# SD_Card.net
KiCad netlist of a schematic drawn in Altium Designer
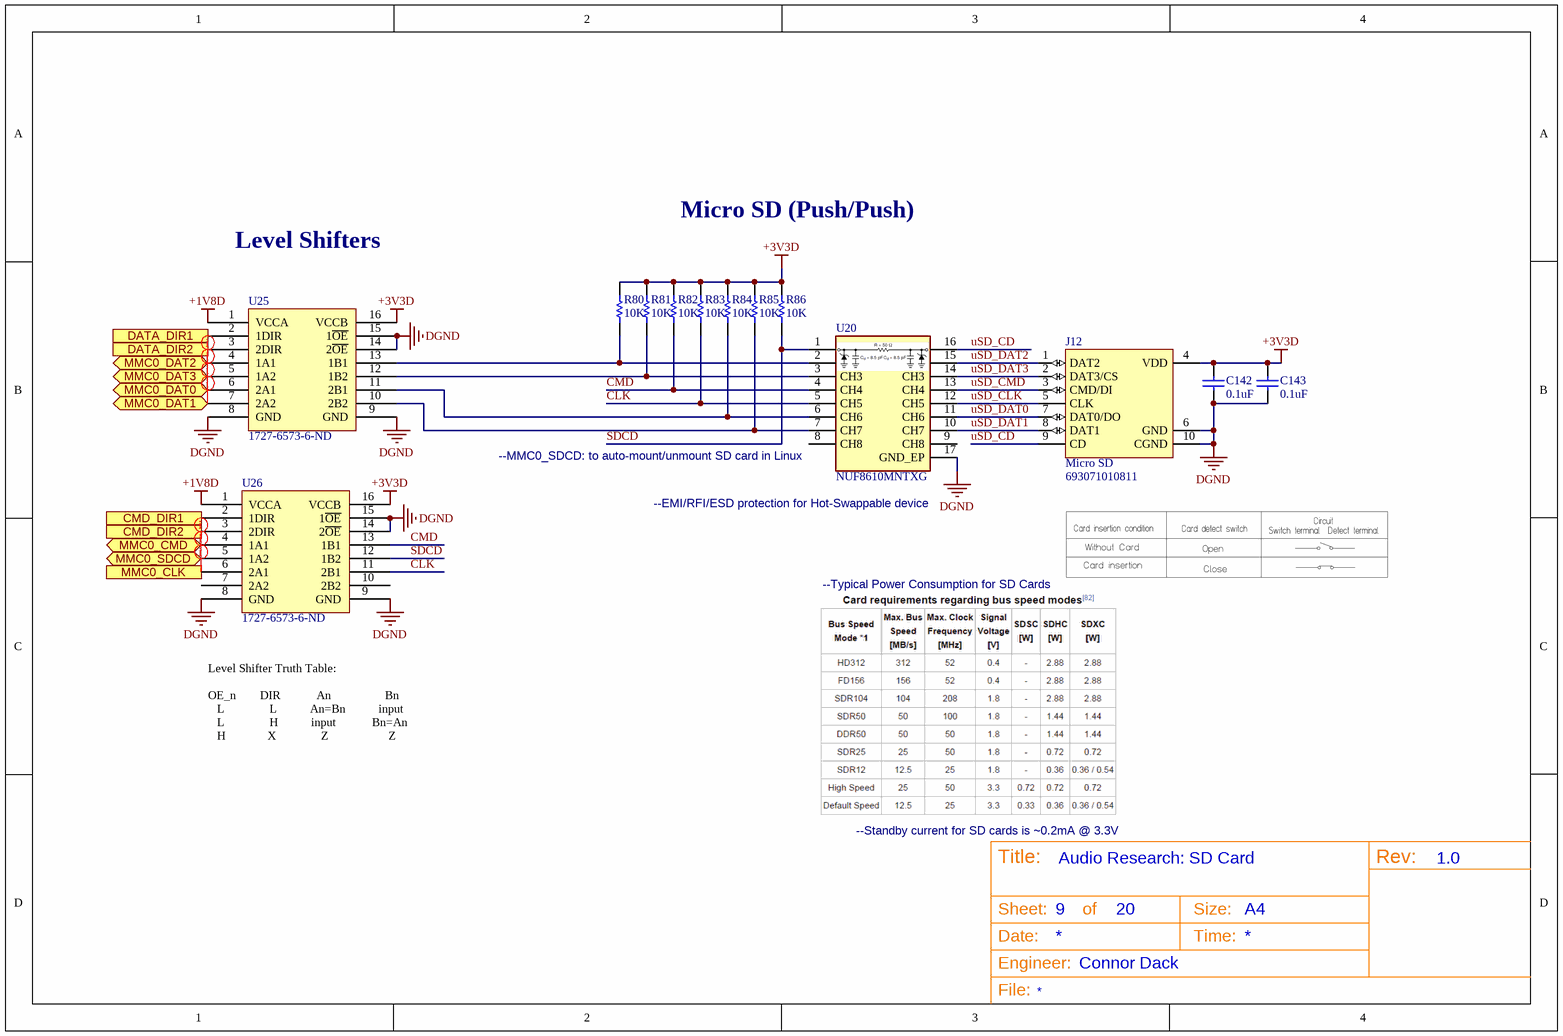
[diagram p0: SD_Card.SchDoc]

(export (version "E")
  (design (tool "Eeschema 10.0.6"))
  (components
    (comp (ref "C142")
      (value "CL10F104ZO8NNNC")
      (footprint "3-0603_L")
      (description "CAP CER 0.1UF 16V Y5V 0603")
      (fields
        (field (name "MANUFACTURER") "Samsung")
        (field (name "TOLERANCE") "80%")
        (field (name "CAPACITANCE") "0.1uF")
      )
      (libsource (lib "Schematic_Components_CD") (part "CL10F104ZO8NNNC"))
    )
    (comp (ref "C143")
      (value "CL10F104ZO8NNNC")
      (footprint "3-0603_L")
      (description "CAP CER 0.1UF 16V Y5V 0603")
      (fields
        (field (name "MANUFACTURER") "Samsung")
        (field (name "TOLERANCE") "80%")
        (field (name "CAPACITANCE") "0.1uF")
      )
      (libsource (lib "Schematic_Components_CD") (part "CL10F104ZO8NNNC"))
    )
    (comp (ref "J12")
      (value "Micro SD")
      (footprint "693071010811")
      (description "CONN MICRO SD 8 POS SMD")
      (fields
        (field (name "MANUFACTURER") "Wurth Electronics Inc")
        (field (name "MANUFACTURER PART NUMBER") "693071010811")
      )
      (libsource (lib "Schematic_Components") (part "693071010811_mmc"))
    )
    (comp (ref "R80")
      (value "ERJ-2GEJ103X")
      (footprint "2-0402_R_L")
      (description "RES 10K OHM 1/10W 5% 0402 SMD")
      (fields
        (field (name "MANUFACTURER") "Panasonic - ECG")
        (field (name "TOLERANCE") "±5%")
        (field (name "RESISTANCE (OHMS)") "10K")
      )
      (libsource (lib "Schematic_Components") (part "ERJ-2GEJ103X"))
    )
    (comp (ref "R81")
      (value "ERJ-2GEJ103X")
      (footprint "2-0402_R_L")
      (description "RES 10K OHM 1/10W 5% 0402 SMD")
      (fields
        (field (name "MANUFACTURER") "Panasonic - ECG")
        (field (name "TOLERANCE") "±5%")
        (field (name "RESISTANCE (OHMS)") "10K")
      )
      (libsource (lib "Schematic_Components") (part "ERJ-2GEJ103X"))
    )
    (comp (ref "R82")
      (value "ERJ-2GEJ103X")
      (footprint "2-0402_R_L")
      (description "RES 10K OHM 1/10W 5% 0402 SMD")
      (fields
        (field (name "MANUFACTURER") "Panasonic - ECG")
        (field (name "TOLERANCE") "±5%")
        (field (name "RESISTANCE (OHMS)") "10K")
      )
      (libsource (lib "Schematic_Components") (part "ERJ-2GEJ103X"))
    )
    (comp (ref "R83")
      (value "ERJ-2GEJ103X")
      (footprint "2-0402_R_L")
      (description "RES 10K OHM 1/10W 5% 0402 SMD")
      (fields
        (field (name "MANUFACTURER") "Panasonic - ECG")
        (field (name "TOLERANCE") "±5%")
        (field (name "RESISTANCE (OHMS)") "10K")
      )
      (libsource (lib "Schematic_Components") (part "ERJ-2GEJ103X"))
    )
    (comp (ref "R84")
      (value "ERJ-2GEJ103X")
      (footprint "2-0402_R_L")
      (description "RES 10K OHM 1/10W 5% 0402 SMD")
      (fields
        (field (name "MANUFACTURER") "Panasonic - ECG")
        (field (name "TOLERANCE") "±5%")
        (field (name "RESISTANCE (OHMS)") "10K")
      )
      (libsource (lib "Schematic_Components") (part "ERJ-2GEJ103X"))
    )
    (comp (ref "R85")
      (value "ERJ-2GEJ103X")
      (footprint "2-0402_R_L")
      (description "RES 10K OHM 1/10W 5% 0402 SMD")
      (fields
        (field (name "MANUFACTURER") "Panasonic - ECG")
        (field (name "TOLERANCE") "±5%")
        (field (name "RESISTANCE (OHMS)") "10K")
      )
      (libsource (lib "Schematic_Components") (part "ERJ-2GEJ103X"))
    )
    (comp (ref "R86")
      (value "ERJ-2GEJ103X")
      (footprint "2-0402_R_L")
      (description "RES 10K OHM 1/10W 5% 0402 SMD")
      (fields
        (field (name "MANUFACTURER") "Panasonic - ECG")
        (field (name "TOLERANCE") "±5%")
        (field (name "RESISTANCE (OHMS)") "10K")
      )
      (libsource (lib "Schematic_Components") (part "ERJ-2GEJ103X"))
    )
    (comp (ref "U20")
      (value "NUF8610MNTXG")
      (footprint "ONSC-DFN-16-506AC_V")
      (description "IC EMI FILTER 8CH 16-DFN")
      (fields
        (field (name "MANUFACTURER") "ON Semiconductor")
        (field (name "MANUFACTURER PART NUMBER") "NUF8610MNTXG")
      )
      (libsource (lib "Schematic_Components") (part "NUF8610MNTXG"))
    )
    (comp (ref "U25")
      (value "IC TXRX 4BIT DUAL 3ST 16TSSOP")
      (footprint "TSOP65P640X120-16N")
      (description "Voltage Level Translator Bidirectional 2 Circuit 2 Channel 380Mbps 16-TSSOP")
      (fields
        (field (name "MANUFACTURER") "NXP Semiconductors")
        (field (name "SUPPLIER PART NUMBER 1") "1727-6573-6-ND")
        (field (name "MANUFACTURER PART NUMBER") "74AVC4T245PW,118")
      )
      (libsource (lib "Schematic_Components_CD") (part "74AVC4T245PW,118"))
    )
    (comp (ref "U26")
      (value "IC TXRX 4BIT DUAL 3ST 16TSSOP")
      (footprint "TSOP65P640X120-16N")
      (description "Voltage Level Translator Bidirectional 2 Circuit 2 Channel 380Mbps 16-TSSOP")
      (fields
        (field (name "MANUFACTURER") "NXP Semiconductors")
        (field (name "SUPPLIER PART NUMBER 1") "1727-6573-6-ND")
        (field (name "MANUFACTURER PART NUMBER") "74AVC4T245PW,118")
      )
      (libsource (lib "Schematic_Components_CD") (part "74AVC4T245PW,118"))
    )
  )
  (nets
    (net (code "1") (name "+1V8D") (class "Default")
      (node (ref "U25") (pin "1") (pinfunction "VCCA_1") (pintype "passive"))
      (node (ref "U26") (pin "1") (pinfunction "VCCA_1") (pintype "passive"))
    )
    (net (code "2") (name "+3V3D") (class "Default")
      (node (ref "C142") (pin "1") (pinfunction "1_1") (pintype "passive"))
      (node (ref "C143") (pin "1") (pinfunction "1_1") (pintype "passive"))
      (node (ref "J12") (pin "4") (pinfunction "VDD_4") (pintype "power_in"))
      (node (ref "R80") (pin "2") (pinfunction "2_2") (pintype "passive"))
      (node (ref "R81") (pin "2") (pinfunction "2_2") (pintype "passive"))
      (node (ref "R82") (pin "2") (pinfunction "2_2") (pintype "passive"))
      (node (ref "R83") (pin "2") (pinfunction "2_2") (pintype "passive"))
      (node (ref "R84") (pin "2") (pinfunction "2_2") (pintype "passive"))
      (node (ref "R85") (pin "2") (pinfunction "2_2") (pintype "passive"))
      (node (ref "R86") (pin "2") (pinfunction "2_2") (pintype "passive"))
      (node (ref "U25") (pin "16") (pinfunction "VCCB_16") (pintype "passive"))
      (node (ref "U26") (pin "16") (pinfunction "VCCB_16") (pintype "passive"))
    )
    (net (code "3") (name "/CLK") (class "Default")
      (node (ref "R83") (pin "1") (pinfunction "1_1") (pintype "passive"))
      (node (ref "U20") (pin "5") (pinfunction "CH5_5") (pintype "passive"))
      (node (ref "U26") (pin "11") (pinfunction "2B1_11") (pintype "passive"))
    )
    (net (code "4") (name "/CMD") (class "Default")
      (node (ref "R82") (pin "1") (pinfunction "1_1") (pintype "passive"))
      (node (ref "U20") (pin "4") (pinfunction "CH4_4") (pintype "passive"))
      (node (ref "U26") (pin "13") (pinfunction "1B1_13") (pintype "passive"))
    )
    (net (code "5") (name "/CMD_DIR1") (class "Default")
      (node (ref "U26") (pin "2") (pinfunction "1DIR_2") (pintype "passive"))
    )
    (net (code "6") (name "/CMD_DIR2") (class "Default")
      (node (ref "U26") (pin "3") (pinfunction "2DIR_3") (pintype "passive"))
    )
    (net (code "7") (name "/DATA_DIR1") (class "Default")
      (node (ref "U25") (pin "2") (pinfunction "1DIR_2") (pintype "passive"))
    )
    (net (code "8") (name "/DATA_DIR2") (class "Default")
      (node (ref "U25") (pin "3") (pinfunction "2DIR_3") (pintype "passive"))
    )
    (net (code "9") (name "/MMC0_CLK") (class "Default")
      (node (ref "U26") (pin "6") (pinfunction "2A1_6") (pintype "passive"))
    )
    (net (code "10") (name "/MMC0_CMD") (class "Default")
      (node (ref "U26") (pin "4") (pinfunction "1A1_4") (pintype "passive"))
    )
    (net (code "11") (name "/MMC0_DAT0") (class "Default")
      (node (ref "U25") (pin "6") (pinfunction "2A1_6") (pintype "passive"))
    )
    (net (code "12") (name "/MMC0_DAT1") (class "Default")
      (node (ref "U25") (pin "7") (pinfunction "2A2_7") (pintype "passive"))
    )
    (net (code "13") (name "/MMC0_DAT2") (class "Default")
      (node (ref "U25") (pin "4") (pinfunction "1A1_4") (pintype "passive"))
    )
    (net (code "14") (name "/MMC0_DAT3") (class "Default")
      (node (ref "U25") (pin "5") (pinfunction "1A2_5") (pintype "passive"))
    )
    (net (code "15") (name "/MMC0_SDCD") (class "Default")
      (node (ref "U26") (pin "5") (pinfunction "1A2_5") (pintype "passive"))
    )
    (net (code "16") (name "/SDCD") (class "Default")
      (node (ref "R86") (pin "1") (pinfunction "1_1") (pintype "passive"))
      (node (ref "U20") (pin "1") (pinfunction "CH1_1") (pintype "passive"))
      (node (ref "U26") (pin "12") (pinfunction "1B2_12") (pintype "passive"))
    )
    (net (code "17") (name "/uSD_CD") (class "Default")
      (node (ref "J12") (pin "9") (pinfunction "CD_9") (pintype "passive"))
      (node (ref "U20") (pin "16") (pinfunction "CH1_16") (pintype "passive"))
    )
    (net (code "18") (name "/uSD_CLK") (class "Default")
      (node (ref "J12") (pin "5") (pinfunction "CLK_5") (pintype "passive"))
      (node (ref "U20") (pin "12") (pinfunction "CH5_12") (pintype "passive"))
    )
    (net (code "19") (name "/uSD_CMD") (class "Default")
      (node (ref "J12") (pin "3") (pinfunction "CMD/DI_3") (pintype "bidirectional"))
      (node (ref "U20") (pin "13") (pinfunction "CH4_13") (pintype "passive"))
    )
    (net (code "20") (name "/uSD_DAT0") (class "Default")
      (node (ref "J12") (pin "7") (pinfunction "DAT0/DO_7") (pintype "bidirectional"))
      (node (ref "U20") (pin "11") (pinfunction "CH6_11") (pintype "passive"))
    )
    (net (code "21") (name "/uSD_DAT1") (class "Default")
      (node (ref "J12") (pin "8") (pinfunction "DAT1_8") (pintype "bidirectional"))
      (node (ref "U20") (pin "10") (pinfunction "CH7_10") (pintype "passive"))
    )
    (net (code "22") (name "/uSD_DAT2") (class "Default")
      (node (ref "J12") (pin "1") (pinfunction "DAT2_1") (pintype "bidirectional"))
      (node (ref "U20") (pin "15") (pinfunction "CH2_15") (pintype "passive"))
    )
    (net (code "23") (name "/uSD_DAT3") (class "Default")
      (node (ref "J12") (pin "2") (pinfunction "DAT3/CS_2") (pintype "bidirectional"))
      (node (ref "U20") (pin "14") (pinfunction "CH3_14") (pintype "passive"))
    )
    (net (code "24") (name "DGND") (class "Default")
      (node (ref "C142") (pin "2") (pinfunction "2_2") (pintype "passive"))
      (node (ref "C143") (pin "2") (pinfunction "2_2") (pintype "passive"))
      (node (ref "J12") (pin "10") (pinfunction "CGND_10") (pintype "passive"))
      (node (ref "J12") (pin "6") (pinfunction "GND_6") (pintype "passive"))
      (node (ref "U20") (pin "17") (pinfunction "GND_EP_17") (pintype "power_in"))
      (node (ref "U25") (pin "14") (pinfunction "2~{OE}_14") (pintype "passive"))
      (node (ref "U25") (pin "15") (pinfunction "1~{OE}_15") (pintype "passive"))
      (node (ref "U25") (pin "8") (pinfunction "GND_8") (pintype "passive"))
      (node (ref "U25") (pin "9") (pinfunction "GND_9") (pintype "passive"))
      (node (ref "U26") (pin "14") (pinfunction "2~{OE}_14") (pintype "passive"))
      (node (ref "U26") (pin "15") (pinfunction "1~{OE}_15") (pintype "passive"))
      (node (ref "U26") (pin "8") (pinfunction "GND_8") (pintype "passive"))
      (node (ref "U26") (pin "9") (pinfunction "GND_9") (pintype "passive"))
    )
    (net (code "25") (name "Net-(U25-1B1)") (class "Default")
      (node (ref "R80") (pin "1") (pinfunction "1_1") (pintype "passive"))
      (node (ref "U20") (pin "2") (pinfunction "CH2_2") (pintype "passive"))
      (node (ref "U25") (pin "13") (pinfunction "1B1_13") (pintype "passive"))
    )
    (net (code "26") (name "Net-(U25-1B2)") (class "Default")
      (node (ref "R81") (pin "1") (pinfunction "1_1") (pintype "passive"))
      (node (ref "U20") (pin "3") (pinfunction "CH3_3") (pintype "passive"))
      (node (ref "U25") (pin "12") (pinfunction "1B2_12") (pintype "passive"))
    )
    (net (code "27") (name "Net-(U25-2B1)") (class "Default")
      (node (ref "R84") (pin "1") (pinfunction "1_1") (pintype "passive"))
      (node (ref "U20") (pin "6") (pinfunction "CH6_6") (pintype "passive"))
      (node (ref "U25") (pin "11") (pinfunction "2B1_11") (pintype "passive"))
    )
    (net (code "28") (name "Net-(U25-2B2)") (class "Default")
      (node (ref "R85") (pin "1") (pinfunction "1_1") (pintype "passive"))
      (node (ref "U20") (pin "7") (pinfunction "CH7_7") (pintype "passive"))
      (node (ref "U25") (pin "10") (pinfunction "2B2_10") (pintype "passive"))
    )
    (net (code "29") (name "unconnected-(U20-CH8-Pad8)") (class "Default")
      (node (ref "U20") (pin "8") (pinfunction "CH8_8") (pintype "passive"))
    )
    (net (code "30") (name "unconnected-(U20-CH8-Pad9)") (class "Default")
      (node (ref "U20") (pin "9") (pinfunction "CH8_9") (pintype "passive"))
    )
    (net (code "31") (name "unconnected-(U26-2A2-Pad7)") (class "Default")
      (node (ref "U26") (pin "7") (pinfunction "2A2_7") (pintype "passive"))
    )
    (net (code "32") (name "unconnected-(U26-2B2-Pad10)") (class "Default")
      (node (ref "U26") (pin "10") (pinfunction "2B2_10") (pintype "passive"))
    )
  )
)
